# powerBoard-2nd.net
KiCad netlist of a schematic drawn in EAGLE
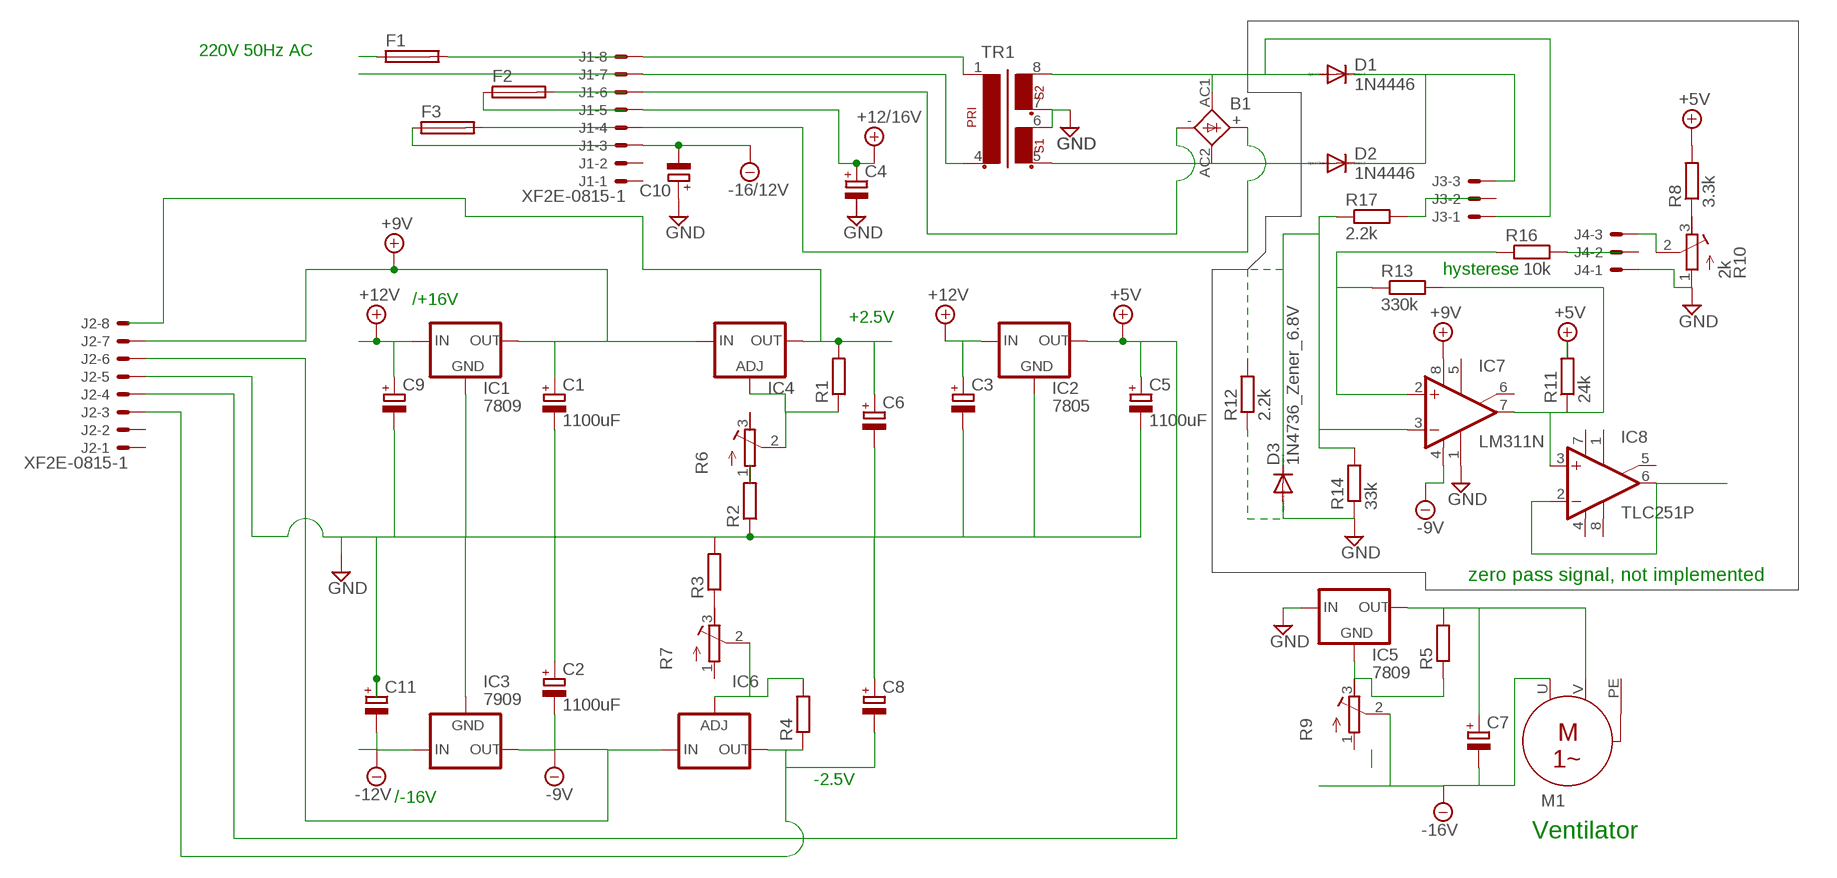
[diagram p0: schematic, sheet 1]

(export (version "E")
  (design (tool "Eeschema 10.0.6"))
  (components
    (comp (ref "B1")
      (value "DSI32A")
      (footprint "eagle-import:DSI32A")
      (libsource (lib "eagle-import") (part "DSI32A"))
    )
    (comp (ref "C1")
      (value "1100uF")
      (footprint "eagle-import:E22-6")
      (libsource (lib "eagle-import") (part "CPOL-EUE22-6AXIAL"))
    )
    (comp (ref "C2")
      (value "1100uF")
      (footprint "eagle-import:E22-6")
      (libsource (lib "eagle-import") (part "CPOL-EUE22-6AXIAL"))
    )
    (comp (ref "C3")
      (value "CPOL-EUE22-6AXIAL")
      (footprint "eagle-import:E22-6")
      (libsource (lib "eagle-import") (part "CPOL-EUE22-6AXIAL"))
    )
    (comp (ref "C4")
      (value "CPOL-EUE22-6AXIAL")
      (footprint "eagle-import:E22-6")
      (libsource (lib "eagle-import") (part "CPOL-EUE22-6AXIAL"))
    )
    (comp (ref "C5")
      (value "1100uF")
      (footprint "eagle-import:E22-6")
      (libsource (lib "eagle-import") (part "CPOL-EUE22-6AXIAL"))
    )
    (comp (ref "C6")
      (value "CPOL-EUE22-6AXIAL")
      (footprint "eagle-import:E22-6")
      (libsource (lib "eagle-import") (part "CPOL-EUE22-6AXIAL"))
    )
    (comp (ref "C7")
      (value "CPOL-EUE22-6AXIAL")
      (footprint "eagle-import:E22-6")
      (libsource (lib "eagle-import") (part "CPOL-EUE22-6AXIAL"))
    )
    (comp (ref "C8")
      (value "CPOL-EUE22-6AXIAL")
      (footprint "eagle-import:E22-6")
      (libsource (lib "eagle-import") (part "CPOL-EUE22-6AXIAL"))
    )
    (comp (ref "C9")
      (value "CPOL-EUE22-6AXIAL")
      (footprint "eagle-import:E22-6")
      (libsource (lib "eagle-import") (part "CPOL-EUE22-6AXIAL"))
    )
    (comp (ref "C10")
      (value "CPOL-EUE22-6AXIAL")
      (footprint "eagle-import:E22-6")
      (libsource (lib "eagle-import") (part "CPOL-EUE22-6AXIAL"))
    )
    (comp (ref "C11")
      (value "CPOL-EUE22-6AXIAL")
      (footprint "eagle-import:E22-6")
      (libsource (lib "eagle-import") (part "CPOL-EUE22-6AXIAL"))
    )
    (comp (ref "D1")
      (value "1N4446")
      (footprint "eagle-import:DO35-10")
      (libsource (lib "eagle-import") (part "1N4446"))
    )
    (comp (ref "D2")
      (value "1N4446")
      (footprint "eagle-import:DO35-10")
      (libsource (lib "eagle-import") (part "1N4446"))
    )
    (comp (ref "D3")
      (value "1N4736_Zener_6.8V")
      (footprint "eagle-import:DO35-10")
      (libsource (lib "eagle-import") (part "1N4446"))
    )
    (comp (ref "F1")
      (value "SH25")
      (footprint "eagle-import:SH25")
      (libsource (lib "eagle-import") (part "SH25"))
    )
    (comp (ref "F2")
      (value "SH25")
      (footprint "eagle-import:SH25")
      (libsource (lib "eagle-import") (part "SH25"))
    )
    (comp (ref "F3")
      (value "SH25")
      (footprint "eagle-import:SH25")
      (libsource (lib "eagle-import") (part "SH25"))
    )
    (comp (ref "IC1")
      (value "7809")
      (footprint "eagle-import:78LXX")
      (libsource (lib "eagle-import") (part "78LXX"))
    )
    (comp (ref "IC2")
      (value "7805")
      (footprint "eagle-import:78LXX")
      (libsource (lib "eagle-import") (part "78LXX"))
    )
    (comp (ref "IC3")
      (value "7909")
      (footprint "eagle-import:79LXX")
      (libsource (lib "eagle-import") (part "79LXX"))
    )
    (comp (ref "IC4")
      (value "LM317-T039")
      (footprint "eagle-import:TO39-H03")
      (libsource (lib "eagle-import") (part "LM317-T039"))
    )
    (comp (ref "IC5")
      (value "7809")
      (footprint "eagle-import:78LXX")
      (libsource (lib "eagle-import") (part "78LXX"))
    )
    (comp (ref "IC6")
      (value "LM337-TO3")
      (footprint "eagle-import:TO3-K02")
      (libsource (lib "eagle-import") (part "LM337-TO3"))
    )
    (comp (ref "IC7")
      (value "LM311N")
      (footprint "eagle-import:DIL08")
      (libsource (lib "eagle-import") (part "LM311N"))
    )
    (comp (ref "IC8")
      (value "TLC251P")
      (footprint "eagle-import:DIL08")
      (libsource (lib "eagle-import") (part "TLC251P"))
    )
    (comp (ref "J1")
      (value "XF2E-0815-1")
      (footprint "eagle-import:XF2E-0815-1")
      (libsource (lib "eagle-import") (part "XF2-08?15-1E"))
    )
    (comp (ref "J2")
      (value "XF2E-0815-1")
      (footprint "eagle-import:XF2E-0815-1")
      (libsource (lib "eagle-import") (part "XF2-08?15-1E"))
    )
    (comp (ref "J3")
      (value "XF2E-0815-1")
      (footprint "eagle-import:XF2E-0815-1")
      (libsource (lib "eagle-import") (part "XF2-08?15-1E"))
    )
    (comp (ref "J4")
      (value "XF2E-0815-1")
      (footprint "eagle-import:XF2E-0815-1")
      (libsource (lib "eagle-import") (part "XF2-08?15-1E"))
    )
    (comp (ref "M1")
      (value "MOTOR_1-PHASEN")
      (footprint "eagle-import:MOTOR_1-PHASEN")
      (libsource (lib "eagle-import") (part "MOTOR_1-PHASEN"))
    )
    (comp (ref "R1")
      (value "R-EU_0309/V")
      (footprint "eagle-import:0309V")
      (libsource (lib "eagle-import") (part "R-EU_0309/V"))
    )
    (comp (ref "R2")
      (value "R-EU_0309/V")
      (footprint "eagle-import:0309V")
      (libsource (lib "eagle-import") (part "R-EU_0309/V"))
    )
    (comp (ref "R3")
      (value "R-EU_0309/V")
      (footprint "eagle-import:0309V")
      (libsource (lib "eagle-import") (part "R-EU_0309/V"))
    )
    (comp (ref "R4")
      (value "R-EU_0309/V")
      (footprint "eagle-import:0309V")
      (libsource (lib "eagle-import") (part "R-EU_0309/V"))
    )
    (comp (ref "R5")
      (value "R-EU_0309/V")
      (footprint "eagle-import:0309V")
      (libsource (lib "eagle-import") (part "R-EU_0309/V"))
    )
    (comp (ref "R6")
      (value "R-TRIMM4G/J")
      (footprint "eagle-import:RTRIM4G_J")
      (libsource (lib "eagle-import") (part "R-TRIMM4G/J"))
    )
    (comp (ref "R7")
      (value "R-TRIMM4G/J")
      (footprint "eagle-import:RTRIM4G_J")
      (libsource (lib "eagle-import") (part "R-TRIMM4G/J"))
    )
    (comp (ref "R8")
      (value "3.3k")
      (footprint "eagle-import:0309V")
      (libsource (lib "eagle-import") (part "R-EU_0309/V"))
    )
    (comp (ref "R9")
      (value "R-TRIMM4G/J")
      (footprint "eagle-import:RTRIM4G_J")
      (libsource (lib "eagle-import") (part "R-TRIMM4G/J"))
    )
    (comp (ref "R10")
      (value "2k")
      (footprint "eagle-import:RTRIM4G_J")
      (libsource (lib "eagle-import") (part "R-TRIMM4G/J"))
    )
    (comp (ref "R11")
      (value "24k")
      (footprint "eagle-import:0309V")
      (libsource (lib "eagle-import") (part "R-EU_0309/V"))
    )
    (comp (ref "R12")
      (value "2.2k")
      (footprint "eagle-import:0309V")
      (libsource (lib "eagle-import") (part "R-EU_0309/V"))
    )
    (comp (ref "R13")
      (value "330k")
      (footprint "eagle-import:0309V")
      (libsource (lib "eagle-import") (part "R-EU_0309/V"))
    )
    (comp (ref "R14")
      (value "33k")
      (footprint "eagle-import:0309V")
      (libsource (lib "eagle-import") (part "R-EU_0309/V"))
    )
    (comp (ref "R16")
      (value "10k")
      (footprint "eagle-import:0309V")
      (libsource (lib "eagle-import") (part "R-EU_0309/V"))
    )
    (comp (ref "R17")
      (value "2.2k")
      (footprint "eagle-import:0309V")
      (libsource (lib "eagle-import") (part "R-EU_0309/V"))
    )
    (comp (ref "TR1")
      (value "EE20-2")
      (footprint "eagle-import:EE20-2")
      (libsource (lib "eagle-import") (part "EE20-2"))
    )
  )
  (nets
    (net (code "1") (name "+5V") (class "Default")
      (node (ref "C5") (pin "+") (pinfunction "+_+") (pintype "passive"))
      (node (ref "IC2") (pin "OUT") (pinfunction "OUT_OUT") (pintype "passive"))
      (node (ref "J2") (pin "4") (pinfunction "MS_4") (pintype "passive"))
      (node (ref "R11") (pin "2") (pinfunction "2_2") (pintype "passive"))
      (node (ref "R8") (pin "2") (pinfunction "2_2") (pintype "passive"))
    )
    (net (code "2") (name "+9V") (class "Default")
      (node (ref "C1") (pin "+") (pinfunction "+_+") (pintype "passive"))
      (node (ref "IC1") (pin "OUT") (pinfunction "OUT_OUT") (pintype "passive"))
      (node (ref "IC4") (pin "1") (pinfunction "IN_1") (pintype "input"))
      (node (ref "IC7") (pin "8") (pinfunction "V+_8") (pintype "power_in"))
      (node (ref "J2") (pin "7") (pinfunction "MS_7") (pintype "passive"))
    )
    (net (code "3") (name "+12V") (class "Default")
      (node (ref "C3") (pin "+") (pinfunction "+_+") (pintype "passive"))
      (node (ref "C4") (pin "+") (pinfunction "+_+") (pintype "passive"))
      (node (ref "C9") (pin "+") (pinfunction "+_+") (pintype "passive"))
      (node (ref "IC1") (pin "IN") (pinfunction "IN_IN") (pintype "input"))
      (node (ref "IC2") (pin "IN") (pinfunction "IN_IN") (pintype "input"))
      (node (ref "J1") (pin "5") (pinfunction "MS_5") (pintype "passive"))
    )
    (net (code "4") (name "-9V") (class "Default")
      (node (ref "C2") (pin "-") (pinfunction "-_-") (pintype "passive"))
      (node (ref "IC3") (pin "OUT") (pinfunction "OUT_OUT") (pintype "passive"))
      (node (ref "IC6") (pin "3") (pinfunction "IN_3") (pintype "input"))
      (node (ref "IC7") (pin "4") (pinfunction "V-_4") (pintype "power_in"))
      (node (ref "J2") (pin "6") (pinfunction "MS_6") (pintype "passive"))
    )
    (net (code "5") (name "-12V") (class "Default")
      (node (ref "C10") (pin "-") (pinfunction "-_-") (pintype "passive"))
      (node (ref "C11") (pin "-") (pinfunction "-_-") (pintype "passive"))
      (node (ref "C7") (pin "-") (pinfunction "-_-") (pintype "passive"))
      (node (ref "IC3") (pin "IN") (pinfunction "IN_IN") (pintype "input"))
      (node (ref "J1") (pin "3") (pinfunction "MS_3") (pintype "passive"))
      (node (ref "M1") (pin "U") (pinfunction "U_U") (pintype "passive"))
      (node (ref "R9") (pin "2") (pinfunction "S_2") (pintype "passive"))
    )
    (net (code "6") (name "/V+") (class "Default")
      (node (ref "IC8") (pin "7") (pinfunction "V+_7") (pintype "power_in"))
    )
    (net (code "7") (name "/V-") (class "Default")
      (node (ref "IC8") (pin "4") (pinfunction "V-_4") (pintype "power_in"))
    )
    (net (code "8") (name "GND") (class "Default")
      (node (ref "C1") (pin "-") (pinfunction "-_-") (pintype "passive"))
      (node (ref "C10") (pin "+") (pinfunction "+_+") (pintype "passive"))
      (node (ref "C11") (pin "+") (pinfunction "+_+") (pintype "passive"))
      (node (ref "C2") (pin "+") (pinfunction "+_+") (pintype "passive"))
      (node (ref "C3") (pin "-") (pinfunction "-_-") (pintype "passive"))
      (node (ref "C5") (pin "-") (pinfunction "-_-") (pintype "passive"))
      (node (ref "C6") (pin "-") (pinfunction "-_-") (pintype "passive"))
      (node (ref "C8") (pin "+") (pinfunction "+_+") (pintype "passive"))
      (node (ref "C9") (pin "-") (pinfunction "-_-") (pintype "passive"))
      (node (ref "D3") (pin "A") (pinfunction "A_A") (pintype "passive"))
      (node (ref "IC1") (pin "GND") (pinfunction "GND_GND") (pintype "input"))
      (node (ref "IC2") (pin "GND") (pinfunction "GND_GND") (pintype "input"))
      (node (ref "IC3") (pin "GND") (pinfunction "GND_GND") (pintype "input"))
      (node (ref "IC5") (pin "IN") (pinfunction "IN_IN") (pintype "input"))
      (node (ref "IC7") (pin "1") (pinfunction "GND_1") (pintype "passive"))
      (node (ref "J2") (pin "5") (pinfunction "MS_5") (pintype "passive"))
      (node (ref "J4") (pin "1") (pinfunction "MSV_1") (pintype "passive"))
      (node (ref "R10") (pin "1") (pinfunction "A_1") (pintype "passive"))
      (node (ref "R12") (pin "1") (pinfunction "1_1") (pintype "passive"))
      (node (ref "R14") (pin "1") (pinfunction "1_1") (pintype "passive"))
      (node (ref "R2") (pin "1") (pinfunction "1_1") (pintype "passive"))
      (node (ref "R3") (pin "2") (pinfunction "2_2") (pintype "passive"))
      (node (ref "TR1") (pin "6") (pinfunction "4_6") (pintype "passive"))
      (node (ref "TR1") (pin "7") (pinfunction "5_7") (pintype "passive"))
    )
    (net (code "9") (name "Net-(C7-Pad+)") (class "Default")
      (node (ref "C7") (pin "+") (pinfunction "+_+") (pintype "passive"))
      (node (ref "IC5") (pin "OUT") (pinfunction "OUT_OUT") (pintype "passive"))
      (node (ref "M1") (pin "V") (pinfunction "V_V") (pintype "passive"))
      (node (ref "R5") (pin "2") (pinfunction "2_2") (pintype "passive"))
    )
    (net (code "10") (name "Net-(IC4-ADJ)") (class "Default")
      (node (ref "IC4") (pin "2") (pinfunction "ADJ_2") (pintype "input"))
      (node (ref "R1") (pin "1") (pinfunction "1_1") (pintype "passive"))
      (node (ref "R6") (pin "2") (pinfunction "S_2") (pintype "passive"))
    )
    (net (code "11") (name "Net-(IC4-OUT)") (class "Default")
      (node (ref "C6") (pin "+") (pinfunction "+_+") (pintype "passive"))
      (node (ref "IC4") (pin "3") (pinfunction "OUT_3") (pintype "passive"))
      (node (ref "J2") (pin "8") (pinfunction "MS_8") (pintype "passive"))
      (node (ref "R1") (pin "2") (pinfunction "2_2") (pintype "passive"))
    )
    (net (code "12") (name "Net-(IC6-ADJ)") (class "Default")
      (node (ref "IC6") (pin "2") (pinfunction "ADJ_2") (pintype "input"))
      (node (ref "R4") (pin "2") (pinfunction "2_2") (pintype "passive"))
      (node (ref "R7") (pin "2") (pinfunction "S_2") (pintype "passive"))
    )
    (net (code "13") (name "Net-(IC6-OUT)") (class "Default")
      (node (ref "C8") (pin "-") (pinfunction "-_-") (pintype "passive"))
      (node (ref "IC6") (pin "1") (pinfunction "OUT_1") (pintype "passive"))
      (node (ref "J2") (pin "3") (pinfunction "MS_3") (pintype "passive"))
      (node (ref "R4") (pin "1") (pinfunction "1_1") (pintype "passive"))
    )
    (net (code "14") (name "Net-(IC7-+IN)") (class "Default")
      (node (ref "IC7") (pin "2") (pinfunction "+IN_2") (pintype "input"))
      (node (ref "R13") (pin "1") (pinfunction "1_1") (pintype "passive"))
      (node (ref "R16") (pin "1") (pinfunction "1_1") (pintype "passive"))
    )
    (net (code "15") (name "Net-(IC7--IN)") (class "Default")
      (node (ref "D3") (pin "C") (pinfunction "C_C") (pintype "passive"))
      (node (ref "IC7") (pin "3") (pinfunction "-IN_3") (pintype "input"))
      (node (ref "R12") (pin "2") (pinfunction "2_2") (pintype "passive"))
      (node (ref "R14") (pin "2") (pinfunction "2_2") (pintype "passive"))
      (node (ref "R17") (pin "1") (pinfunction "1_1") (pintype "passive"))
    )
    (net (code "16") (name "Net-(IC7-OUT)") (class "Default")
      (node (ref "IC7") (pin "7") (pinfunction "OUT_7") (pintype "output"))
      (node (ref "IC8") (pin "3") (pinfunction "+IN_3") (pintype "input"))
      (node (ref "R11") (pin "1") (pinfunction "1_1") (pintype "passive"))
      (node (ref "R13") (pin "2") (pinfunction "2_2") (pintype "passive"))
    )
    (net (code "17") (name "Net-(IC8--IN)") (class "Default")
      (node (ref "IC8") (pin "2") (pinfunction "-IN_2") (pintype "input"))
      (node (ref "IC8") (pin "6") (pinfunction "OUT_6") (pintype "output"))
    )
    (net (code "18") (name "Net-(J1D-MS)") (class "Default")
      (node (ref "B1") (pin "+") (pinfunction "+_+") (pintype "passive"))
      (node (ref "J1") (pin "4") (pinfunction "MS_4") (pintype "passive"))
    )
    (net (code "19") (name "Net-(J1F-MS)") (class "Default")
      (node (ref "B1") (pin "-") (pinfunction "-_-") (pintype "passive"))
      (node (ref "J1") (pin "6") (pinfunction "MS_6") (pintype "passive"))
    )
    (net (code "20") (name "Net-(J1G-MS)") (class "Default")
      (node (ref "J1") (pin "7") (pinfunction "MS_7") (pintype "passive"))
      (node (ref "TR1") (pin "4") (pinfunction "2_4") (pintype "passive"))
    )
    (net (code "21") (name "Net-(J1H-MS)") (class "Default")
      (node (ref "J1") (pin "8") (pinfunction "MS_8") (pintype "passive"))
      (node (ref "TR1") (pin "1") (pinfunction "1_1") (pintype "passive"))
    )
    (net (code "22") (name "Net-(J3A-MSV)") (class "Default")
      (node (ref "B1") (pin "AC1") (pinfunction "AC1_AC1") (pintype "passive"))
      (node (ref "D1") (pin "A") (pinfunction "A_A") (pintype "passive"))
      (node (ref "J3") (pin "1") (pinfunction "MSV_1") (pintype "passive"))
      (node (ref "TR1") (pin "8") (pinfunction "6_8") (pintype "passive"))
    )
    (net (code "23") (name "Net-(J3C-MS)") (class "Default")
      (node (ref "D1") (pin "C") (pinfunction "C_C") (pintype "passive"))
      (node (ref "D2") (pin "C") (pinfunction "C_C") (pintype "passive"))
      (node (ref "J3") (pin "3") (pinfunction "MS_3") (pintype "passive"))
    )
    (net (code "24") (name "Net-(J4C-MS)") (class "Default")
      (node (ref "J4") (pin "3") (pinfunction "MS_3") (pintype "passive"))
      (node (ref "R10") (pin "2") (pinfunction "S_2") (pintype "passive"))
    )
    (net (code "25") (name "Net-(R6-A)") (class "Default")
      (node (ref "R2") (pin "2") (pinfunction "2_2") (pintype "passive"))
      (node (ref "R6") (pin "1") (pinfunction "A_1") (pintype "passive"))
    )
    (net (code "26") (name "Net-(R7-E)") (class "Default")
      (node (ref "R3") (pin "1") (pinfunction "1_1") (pintype "passive"))
      (node (ref "R7") (pin "3") (pinfunction "E_3") (pintype "passive"))
    )
    (net (code "27") (name "Net-(R9-E)") (class "Default")
      (node (ref "IC5") (pin "GND") (pinfunction "GND_GND") (pintype "input"))
      (node (ref "R5") (pin "1") (pinfunction "1_1") (pintype "passive"))
      (node (ref "R9") (pin "3") (pinfunction "E_3") (pintype "passive"))
    )
    (net (code "28") (name "Net-(R10-E)") (class "Default")
      (node (ref "R10") (pin "3") (pinfunction "E_3") (pintype "passive"))
      (node (ref "R8") (pin "1") (pinfunction "1_1") (pintype "passive"))
    )
    (net (code "29") (name "Net-(TR1-3)") (class "Default")
      (node (ref "B1") (pin "AC2") (pinfunction "AC2_AC2") (pintype "passive"))
      (node (ref "TR1") (pin "5") (pinfunction "3_5") (pintype "passive"))
    )
    (net (code "30") (name "unconnected-(C4-Pad-)") (class "Default")
      (node (ref "C4") (pin "-") (pinfunction "-_-") (pintype "passive"))
    )
    (net (code "31") (name "unconnected-(D2-PadA)") (class "Default")
      (node (ref "D2") (pin "A") (pinfunction "A_A") (pintype "passive"))
    )
    (net (code "32") (name "unconnected-(F1-Pad1)") (class "Default")
      (node (ref "F1") (pin "1") (pinfunction "1_1") (pintype "passive"))
    )
    (net (code "33") (name "unconnected-(F1-Pad2)") (class "Default")
      (node (ref "F1") (pin "2") (pinfunction "2_2") (pintype "passive"))
    )
    (net (code "34") (name "unconnected-(F2-Pad1)") (class "Default")
      (node (ref "F2") (pin "1") (pinfunction "1_1") (pintype "passive"))
    )
    (net (code "35") (name "unconnected-(F2-Pad2)") (class "Default")
      (node (ref "F2") (pin "2") (pinfunction "2_2") (pintype "passive"))
    )
    (net (code "36") (name "unconnected-(F3-Pad1)") (class "Default")
      (node (ref "F3") (pin "1") (pinfunction "1_1") (pintype "passive"))
    )
    (net (code "37") (name "unconnected-(F3-Pad2)") (class "Default")
      (node (ref "F3") (pin "2") (pinfunction "2_2") (pintype "passive"))
    )
    (net (code "38") (name "unconnected-(IC7-ON-Pad5)") (class "Default")
      (node (ref "IC7") (pin "5") (pinfunction "ON_5") (pintype "passive"))
    )
    (net (code "39") (name "unconnected-(IC7-ON{slash}STR-Pad6)") (class "Default")
      (node (ref "IC7") (pin "6") (pinfunction "ON/STR_6") (pintype "passive"))
    )
    (net (code "40") (name "unconnected-(IC8-ON1-Pad1)") (class "Default")
      (node (ref "IC8") (pin "1") (pinfunction "ON1_1") (pintype "passive"))
    )
    (net (code "41") (name "unconnected-(IC8-ON2-Pad5)") (class "Default")
      (node (ref "IC8") (pin "5") (pinfunction "ON2_5") (pintype "passive"))
    )
    (net (code "42") (name "unconnected-(IC8-OPT-Pad8)") (class "Default")
      (node (ref "IC8") (pin "8") (pinfunction "OPT_8") (pintype "passive"))
    )
    (net (code "43") (name "unconnected-(J1A-MSV-Pad1)") (class "Default")
      (node (ref "J1") (pin "1") (pinfunction "MSV_1") (pintype "passive"))
    )
    (net (code "44") (name "unconnected-(J1B-MS-Pad2)") (class "Default")
      (node (ref "J1") (pin "2") (pinfunction "MS_2") (pintype "passive"))
    )
    (net (code "45") (name "unconnected-(J2A-MSV-Pad1)") (class "Default")
      (node (ref "J2") (pin "1") (pinfunction "MSV_1") (pintype "passive"))
    )
    (net (code "46") (name "unconnected-(J2B-MS-Pad2)") (class "Default")
      (node (ref "J2") (pin "2") (pinfunction "MS_2") (pintype "passive"))
    )
    (net (code "47") (name "unconnected-(J3B-MS-Pad2)") (class "Default")
      (node (ref "J3") (pin "2") (pinfunction "MS_2") (pintype "passive"))
    )
    (net (code "48") (name "unconnected-(J4B-MS-Pad2)") (class "Default")
      (node (ref "J4") (pin "2") (pinfunction "MS_2") (pintype "passive"))
    )
    (net (code "49") (name "unconnected-(M1-PadPE)") (class "Default")
      (node (ref "M1") (pin "PE") (pinfunction "PE_PE") (pintype "passive"))
    )
    (net (code "50") (name "unconnected-(R6-E-Pad3)") (class "Default")
      (node (ref "R6") (pin "3") (pinfunction "E_3") (pintype "passive"))
    )
    (net (code "51") (name "unconnected-(R7-A-Pad1)") (class "Default")
      (node (ref "R7") (pin "1") (pinfunction "A_1") (pintype "passive"))
    )
    (net (code "52") (name "unconnected-(R9-A-Pad1)") (class "Default")
      (node (ref "R9") (pin "1") (pinfunction "A_1") (pintype "passive"))
    )
    (net (code "53") (name "unconnected-(R16-Pad2)") (class "Default")
      (node (ref "R16") (pin "2") (pinfunction "2_2") (pintype "passive"))
    )
    (net (code "54") (name "unconnected-(R17-Pad2)") (class "Default")
      (node (ref "R17") (pin "2") (pinfunction "2_2") (pintype "passive"))
    )
  )
)
